# Robotic_armmodified_3pin.net
KiCad netlist of a schematic drawn in EAGLE
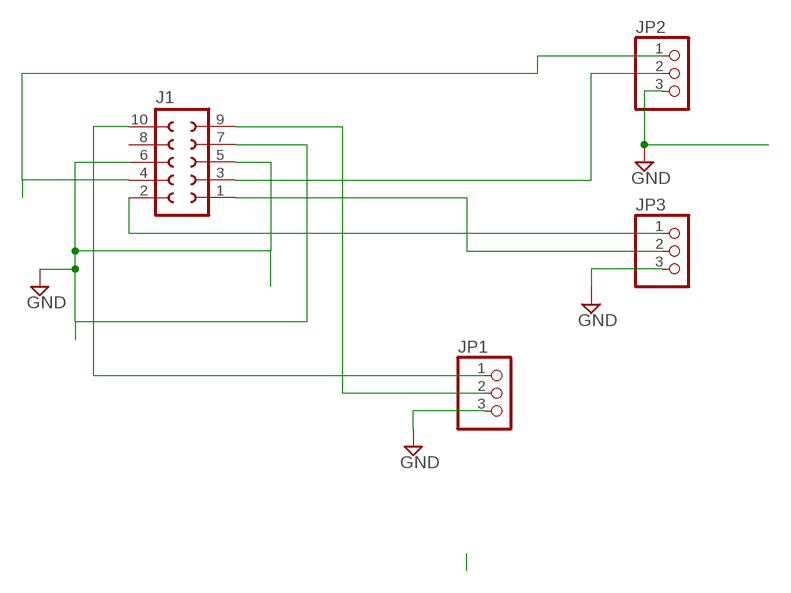
[diagram p0: schematic, sheet 1]

(export (version "E")
  (design (tool "Eeschema 10.0.6"))
  (components
    (comp (ref "J1")
      (value "SOCKET-10V")
      (footprint "eagle-import:S10V")
      (libsource (lib "eagle-import") (part "SOCKET-10V"))
    )
    (comp (ref "JP1")
      (value "PINHD-1X3")
      (footprint "eagle-import:1X03")
      (libsource (lib "eagle-import") (part "PINHD-1X3"))
    )
    (comp (ref "JP2")
      (value "PINHD-1X3")
      (footprint "eagle-import:1X03")
      (libsource (lib "eagle-import") (part "PINHD-1X3"))
    )
    (comp (ref "JP3")
      (value "PINHD-1X3")
      (footprint "eagle-import:1X03")
      (libsource (lib "eagle-import") (part "PINHD-1X3"))
    )
    (comp (ref "MRM1")
      (value "MRM")
      (footprint "eagle-import:LOL")
      (libsource (lib "eagle-import") (part "MRM"))
    )
  )
  (nets
    (net (code "1") (name "GND") (class "Default")
      (node (ref "J1") (pin "5") (pinfunction "5_5") (pintype "passive"))
      (node (ref "J1") (pin "6") (pinfunction "6_6") (pintype "passive"))
      (node (ref "J1") (pin "7") (pinfunction "7_7") (pintype "passive"))
      (node (ref "JP1") (pin "3") (pinfunction "3_3") (pintype "passive"))
      (node (ref "JP2") (pin "3") (pinfunction "3_3") (pintype "passive"))
      (node (ref "JP3") (pin "3") (pinfunction "3_3") (pintype "passive"))
    )
    (net (code "2") (name "Net-(J1-Pad1)") (class "Default")
      (node (ref "J1") (pin "1") (pinfunction "1_1") (pintype "passive"))
      (node (ref "JP3") (pin "2") (pinfunction "2_2") (pintype "passive"))
    )
    (net (code "3") (name "Net-(J1-Pad2)") (class "Default")
      (node (ref "J1") (pin "2") (pinfunction "2_2") (pintype "passive"))
      (node (ref "JP3") (pin "1") (pinfunction "1_1") (pintype "passive"))
    )
    (net (code "4") (name "Net-(J1-Pad3)") (class "Default")
      (node (ref "J1") (pin "3") (pinfunction "3_3") (pintype "passive"))
      (node (ref "JP2") (pin "2") (pinfunction "2_2") (pintype "passive"))
    )
    (net (code "5") (name "Net-(J1-Pad4)") (class "Default")
      (node (ref "J1") (pin "4") (pinfunction "4_4") (pintype "passive"))
      (node (ref "JP2") (pin "1") (pinfunction "1_1") (pintype "passive"))
    )
    (net (code "6") (name "Net-(J1-Pad9)") (class "Default")
      (node (ref "J1") (pin "9") (pinfunction "9_9") (pintype "passive"))
      (node (ref "JP1") (pin "2") (pinfunction "2_2") (pintype "passive"))
    )
    (net (code "7") (name "Net-(J1-Pad10)") (class "Default")
      (node (ref "J1") (pin "10") (pinfunction "10_10") (pintype "passive"))
      (node (ref "JP1") (pin "1") (pinfunction "1_1") (pintype "passive"))
    )
    (net (code "8") (name "unconnected-(J1-Pad8)") (class "Default")
      (node (ref "J1") (pin "8") (pinfunction "8_8") (pintype "passive"))
    )
  )
)
